# ST_LINK_V2.net
KiCad netlist of a schematic drawn in Altium Designer
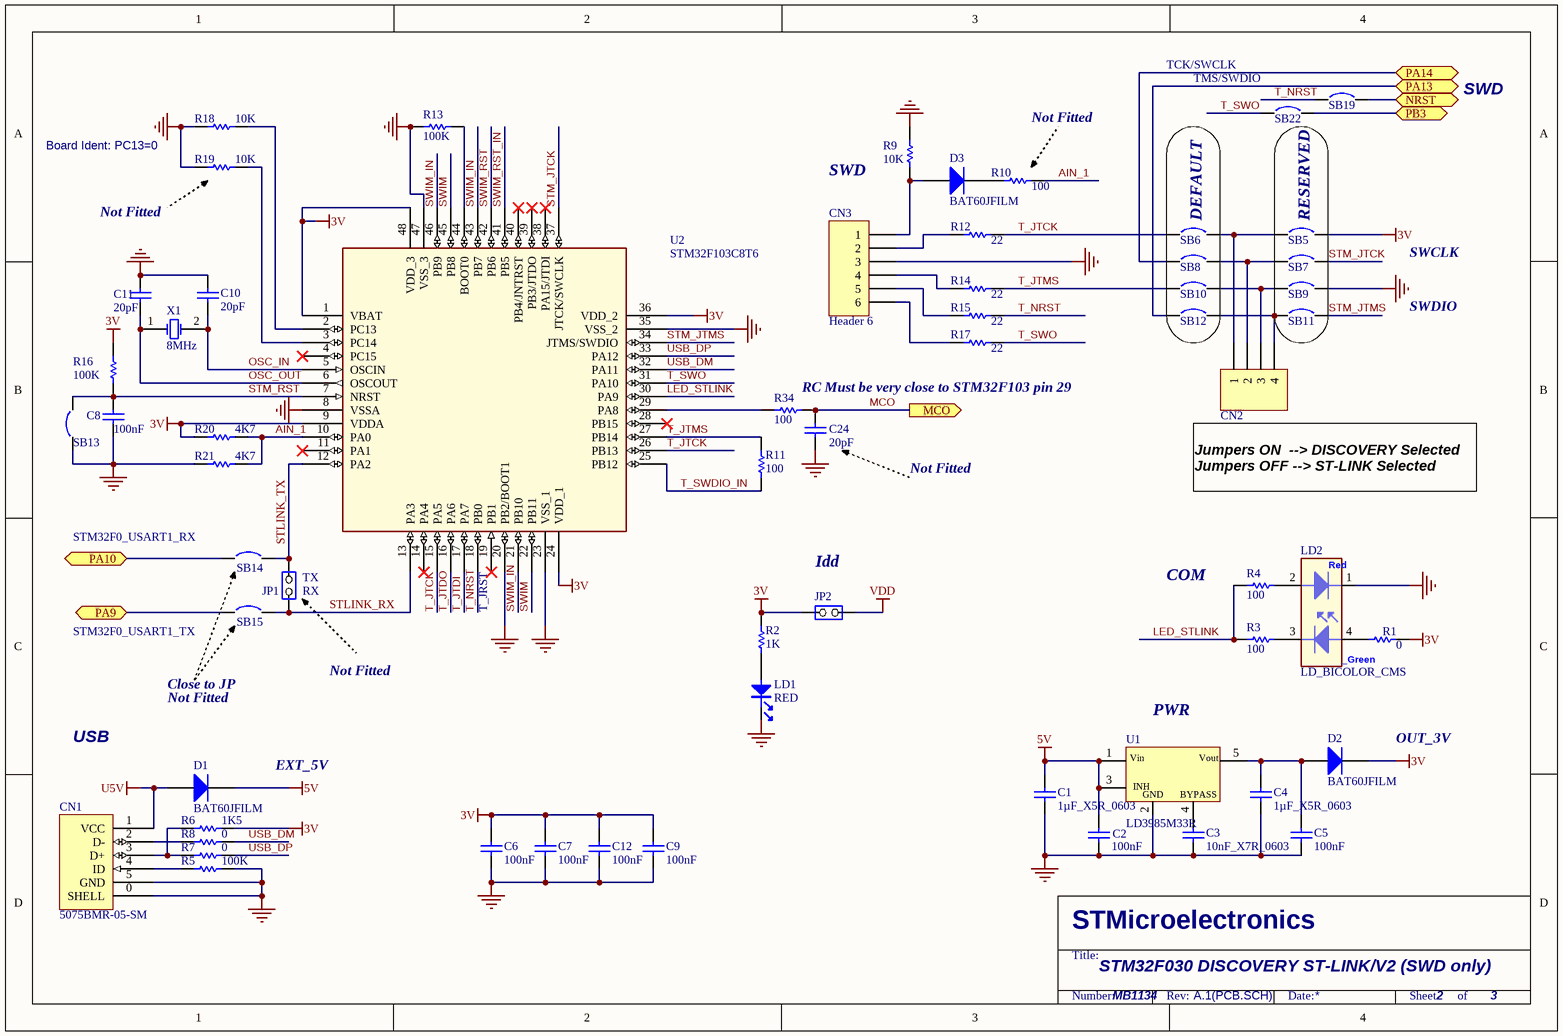
[diagram p0: ST_LINK_V2.SCHDOC]

(export (version "E")
  (design (tool "Eeschema 10.0.6"))
  (components
    (comp (ref "C1")
      (value "1µF_X5R_0603")
      (footprint "0603C")
      (description "0603  X5R 1µF")
      (fields (field (name "TOLERANCE") "10%"))
      (libsource (lib "MCD_TOOLS") (part "CAP SMD 0603  X5R 1µF 25V 10%"))
    )
    (comp (ref "C2")
      (value "100nF")
      (footprint "0603C")
      (description "Capacitor")
      (fields (field (name "PUBLISHER") "Altium Limited"))
      (libsource (lib "MCD_TOOLS") (part "Cap"))
    )
    (comp (ref "C3")
      (value "10nF_X7R_0603")
      (footprint "0603C")
      (description "0603  X7R 10NF")
      (fields (field (name "TOLERANCE") "10%"))
      (libsource (lib "MCD_TOOLS") (part "CAP SMD 0603  X7R 10000PF 50V 10%"))
    )
    (comp (ref "C4")
      (value "1µF_X5R_0603")
      (footprint "0603C")
      (description "0603  X5R 1µF")
      (fields (field (name "TOLERANCE") "10%"))
      (libsource (lib "MCD_TOOLS") (part "CAP SMD 0603  X5R 1µF 25V 10%"))
    )
    (comp (ref "C5")
      (value "100nF")
      (footprint "0603C")
      (description "Capacitor")
      (fields (field (name "PUBLISHER") "Altium Limited"))
      (libsource (lib "MCD_TOOLS") (part "Cap"))
    )
    (comp (ref "C6")
      (value "100nF")
      (footprint "0402C")
      (description "Capacitor")
      (fields (field (name "PUBLISHER") "Altium Limited"))
      (libsource (lib "MCD_TOOLS") (part "Cap"))
    )
    (comp (ref "C7")
      (value "100nF")
      (footprint "0402C")
      (description "Capacitor")
      (fields (field (name "PUBLISHER") "Altium Limited"))
      (libsource (lib "MCD_TOOLS") (part "Cap"))
    )
    (comp (ref "C8")
      (value "100nF")
      (footprint "0402C")
      (description "Capacitor")
      (fields (field (name "PUBLISHER") "Altium Limited"))
      (libsource (lib "MCD_TOOLS") (part "Cap"))
    )
    (comp (ref "C9")
      (value "100nF")
      (footprint "0402C")
      (description "Capacitor")
      (fields (field (name "PUBLISHER") "Altium Limited"))
      (libsource (lib "MCD_TOOLS") (part "Cap"))
    )
    (comp (ref "C10")
      (value "20pF")
      (footprint "0402C")
      (description "Capacitor")
      (fields (field (name "PUBLISHER") "Altium Limited"))
      (libsource (lib "MCD_TOOLS") (part "Cap"))
    )
    (comp (ref "C11")
      (value "20pF")
      (footprint "0402C")
      (description "Capacitor")
      (fields (field (name "PUBLISHER") "Altium Limited"))
      (libsource (lib "MCD_TOOLS") (part "Cap"))
    )
    (comp (ref "C12")
      (value "100nF")
      (footprint "0402C")
      (description "Capacitor")
      (fields (field (name "PUBLISHER") "Altium Limited"))
      (libsource (lib "MCD_TOOLS") (part "Cap"))
    )
    (comp (ref "C24")
      (value "20pF")
      (footprint "0402C")
      (description "Capacitor")
      (fields (field (name "PUBLISHER") "Altium Limited"))
      (libsource (lib "MCD_TOOLS") (part "Cap"))
    )
    (comp (ref "CN1")
      (value "5075BMR-05-SM")
      (footprint "USB-MINI-B-SMD")
      (libsource (lib "MCD_TOOLS") (part "USB-MINI-typeB connector"))
    )
    (comp (ref "CN2")
      (value "Header 4")
      (footprint "Header 4")
      (description "Header 4x1 with 2 Jumpers")
      (fields (field (name "PUBLISHER") "Altium Limited"))
      (libsource (lib "MCD_TOOLS") (part "Header 4"))
    )
    (comp (ref "CN3")
      (value "Header 6")
      (footprint "HDR1X6")
      (description "Header, 6-Pin")
      (fields (field (name "PUBLISHER") "Altium Limited"))
      (libsource (lib "Miscellaneous Connectors") (part "Header 6"))
    )
    (comp (ref "D1")
      (value "BAT60JFILM")
      (footprint "SOD323/A")
      (fields (field (name "PUBLISHER") "Altium Limited"))
      (libsource (lib "MCD_TOOLS") (part "BAT60JFILM"))
    )
    (comp (ref "D2")
      (value "BAT60JFILM")
      (footprint "SOD323/A")
      (fields (field (name "PUBLISHER") "Altium Limited"))
      (libsource (lib "MCD_TOOLS") (part "BAT60JFILM"))
    )
    (comp (ref "D3")
      (value "BAT60JFILM")
      (footprint "SOD323/A")
      (fields (field (name "PUBLISHER") "Altium Limited"))
      (libsource (lib "MCD_TOOLS") (part "BAT60JFILM"))
    )
    (comp (ref "JP1") (value "~") (footprint "SIP2/2.54") (libsource (lib "MCD_TOOLS") (part "JP2")))
    (comp (ref "JP2")
      (value "~")
      (footprint "SIP2/2.54")
      (description "Header 2x1 with Jumper")
      (libsource (lib "MCD_TOOLS") (part "JP2"))
    )
    (comp (ref "LD1") (value "RED") (footprint "0603D") (libsource (lib "MCD_TOOLS") (part "PHOTO")))
    (comp (ref "LD2")
      (value "LD_BICOLOR_CMS")
      (footprint "HSMF-A201")
      (description "Bicolor Led")
      (libsource (lib "MCD_TOOLS") (part "LD_BICOLOR_CMS"))
    )
    (comp (ref "R1")
      (value "0")
      (footprint "0402R")
      (description "Resistor")
      (fields (field (name "PUBLISHER") "Altium Limited"))
      (libsource (lib "MCD_TOOLS") (part "res1"))
    )
    (comp (ref "R2")
      (value "1K")
      (footprint "0402R")
      (description "Resistor")
      (fields (field (name "PUBLISHER") "Altium Limited"))
      (libsource (lib "MCD_TOOLS") (part "res1"))
    )
    (comp (ref "R3")
      (value "100")
      (footprint "0402R")
      (description "Resistor")
      (fields (field (name "PUBLISHER") "Altium Limited"))
      (libsource (lib "MCD_TOOLS") (part "res1"))
    )
    (comp (ref "R4")
      (value "100")
      (footprint "0402R")
      (description "Resistor")
      (fields (field (name "PUBLISHER") "Altium Limited"))
      (libsource (lib "MCD_TOOLS") (part "res1"))
    )
    (comp (ref "R5")
      (value "100K")
      (footprint "0402R")
      (description "Resistor")
      (fields (field (name "PUBLISHER") "Altium Limited"))
      (libsource (lib "MB915_1") (part "res1"))
    )
    (comp (ref "R6")
      (value "1K5")
      (footprint "0402R")
      (description "Resistor")
      (fields (field (name "PUBLISHER") "Altium Limited"))
      (libsource (lib "MB915_1") (part "res1"))
    )
    (comp (ref "R7")
      (value "0")
      (footprint "0603R-GS")
      (description "Resistor")
      (fields (field (name "PUBLISHER") "Altium Limited"))
      (libsource (lib "MB915_1") (part "res1"))
    )
    (comp (ref "R8")
      (value "0")
      (footprint "0603R-GS")
      (description "Resistor")
      (fields (field (name "PUBLISHER") "Altium Limited"))
      (libsource (lib "MB915_1") (part "res1"))
    )
    (comp (ref "R9")
      (value "10K")
      (footprint "0402R")
      (description "Resistor")
      (fields (field (name "PUBLISHER") "Altium Limited"))
      (libsource (lib "MB915_1") (part "res1"))
    )
    (comp (ref "R10")
      (value "100")
      (footprint "0402R")
      (description "Resistor")
      (fields (field (name "PUBLISHER") "Altium Limited"))
      (libsource (lib "MCD_TOOLS") (part "res1"))
    )
    (comp (ref "R11")
      (value "100")
      (footprint "0402R")
      (description "Resistor")
      (fields (field (name "PUBLISHER") "Altium Limited"))
      (libsource (lib "MCD_TOOLS") (part "res1"))
    )
    (comp (ref "R12")
      (value "22")
      (footprint "0402R")
      (description "Resistor")
      (fields (field (name "PUBLISHER") "Altium Limited"))
      (libsource (lib "MCD_TOOLS") (part "res1"))
    )
    (comp (ref "R13")
      (value "100K")
      (footprint "0402R")
      (description "Resistor")
      (fields (field (name "PUBLISHER") "Altium Limited"))
      (libsource (lib "MCD_TOOLS") (part "res1"))
    )
    (comp (ref "R14")
      (value "22")
      (footprint "0402R")
      (description "Resistor")
      (fields (field (name "PUBLISHER") "Altium Limited"))
      (libsource (lib "MCD_TOOLS") (part "res1"))
    )
    (comp (ref "R15")
      (value "22")
      (footprint "0402R")
      (description "Resistor")
      (fields (field (name "PUBLISHER") "Altium Limited"))
      (libsource (lib "MCD_TOOLS") (part "res1"))
    )
    (comp (ref "R16")
      (value "100K")
      (footprint "0402R")
      (description "Resistor")
      (fields (field (name "PUBLISHER") "Altium Limited"))
      (libsource (lib "MCD_TOOLS") (part "res1"))
    )
    (comp (ref "R17")
      (value "22")
      (footprint "0402R")
      (description "Resistor")
      (fields (field (name "PUBLISHER") "Altium Limited"))
      (libsource (lib "MCD_TOOLS") (part "res1"))
    )
    (comp (ref "R18")
      (value "10K")
      (footprint "0402R")
      (description "Resistor")
      (fields (field (name "PUBLISHER") "Altium Limited"))
      (libsource (lib "MCD_TOOLS") (part "res1"))
    )
    (comp (ref "R19")
      (value "10K")
      (footprint "0402R")
      (description "Resistor")
      (fields (field (name "PUBLISHER") "Altium Limited"))
      (libsource (lib "MCD_TOOLS") (part "res1"))
    )
    (comp (ref "R20")
      (value "4K7")
      (footprint "0402R")
      (description "Resistor")
      (fields (field (name "PUBLISHER") "Altium Limited"))
      (libsource (lib "MCD_TOOLS") (part "res1"))
    )
    (comp (ref "R21")
      (value "4K7")
      (footprint "0402R")
      (description "Resistor")
      (fields (field (name "PUBLISHER") "Altium Limited"))
      (libsource (lib "MCD_TOOLS") (part "res1"))
    )
    (comp (ref "R34")
      (value "100")
      (footprint "0402R")
      (description "Resistor")
      (fields (field (name "PUBLISHER") "Altium Limited"))
      (libsource (lib "MCD_TOOLS") (part "res1"))
    )
    (comp (ref "SB5")
      (value "Circuit Breaker")
      (footprint "JP2_SMD")
      (fields (field (name "PUBLISHER") "Altium Limited"))
      (libsource (lib "MB915") (part "Circuit Breaker"))
    )
    (comp (ref "SB6")
      (value "Circuit Breaker")
      (footprint "JP2_SMD")
      (fields (field (name "PUBLISHER") "Altium Limited"))
      (libsource (lib "MB915") (part "Circuit Breaker"))
    )
    (comp (ref "SB7")
      (value "Circuit Breaker")
      (footprint "JP2_SMD")
      (fields (field (name "PUBLISHER") "Altium Limited"))
      (libsource (lib "MB915") (part "Circuit Breaker"))
    )
    (comp (ref "SB8")
      (value "Circuit Breaker")
      (footprint "JP2_SMD")
      (fields (field (name "PUBLISHER") "Altium Limited"))
      (libsource (lib "MB915") (part "Circuit Breaker"))
    )
    (comp (ref "SB9")
      (value "Circuit Breaker")
      (footprint "JP2_SMD")
      (fields (field (name "PUBLISHER") "Altium Limited"))
      (libsource (lib "MB915") (part "Circuit Breaker"))
    )
    (comp (ref "SB10")
      (value "Circuit Breaker")
      (footprint "JP2_SMD")
      (fields (field (name "PUBLISHER") "Altium Limited"))
      (libsource (lib "MB915") (part "Circuit Breaker"))
    )
    (comp (ref "SB11")
      (value "Circuit Breaker")
      (footprint "JP2_SMD")
      (fields (field (name "PUBLISHER") "Altium Limited"))
      (libsource (lib "MB915") (part "Circuit Breaker"))
    )
    (comp (ref "SB12")
      (value "Circuit Breaker")
      (footprint "JP2_SMD")
      (fields (field (name "PUBLISHER") "Altium Limited"))
      (libsource (lib "MB915") (part "Circuit Breaker"))
    )
    (comp (ref "SB13")
      (value "Circuit Breaker")
      (footprint "JP2_SMD")
      (fields (field (name "PUBLISHER") "Altium Limited"))
      (libsource (lib "MCD_TOOLS") (part "Circuit Breaker"))
    )
    (comp (ref "SB14")
      (value "Circuit Breaker")
      (footprint "JP2_SMD")
      (fields (field (name "PUBLISHER") "Altium Limited"))
      (libsource (lib "MCD_TOOLS") (part "Circuit Breaker"))
    )
    (comp (ref "SB15")
      (value "Circuit Breaker")
      (footprint "JP2_SMD")
      (fields (field (name "PUBLISHER") "Altium Limited"))
      (libsource (lib "MCD_TOOLS") (part "Circuit Breaker"))
    )
    (comp (ref "SB19")
      (value "Circuit Breaker")
      (footprint "JP2_SMD")
      (fields (field (name "PUBLISHER") "Altium Limited"))
      (libsource (lib "MCD_TOOLS") (part "Circuit Breaker"))
    )
    (comp (ref "SB22")
      (value "Circuit Breaker")
      (footprint "JP2_SMD")
      (fields (field (name "PUBLISHER") "Altium Limited"))
      (libsource (lib "MCD_TOOLS") (part "Circuit Breaker"))
    )
    (comp (ref "U1")
      (value "LD3985M33R")
      (footprint "SOT-23-5L")
      (description "Ultra low drop-low noise BiCMOS voltage, regulators low ESR capacitors compatible")
      (libsource (lib "MCD_TOOLS") (part "LD3985M33R"))
    )
    (comp (ref "U2")
      (value "STM32F103C8T6")
      (footprint "QFP48 7X7")
      (description "Medium-density performance line ARM-based 32-bit MCU with 64KB Flash, USB, CAN, 7 timers, 2 ADCs")
      (libsource (lib "MCD_TOOLS") (part "STM32F103C8T6"))
    )
    (comp (ref "X1")
      (value "8MHz")
      (footprint "XTAL1")
      (description "Crystal Oscillator")
      (fields (field (name "PUBLISHER") "Altium Limited"))
      (libsource (lib "MCD_TOOLS") (part "XTAL"))
    )
  )
  (nets
    (net (code "1") (name "/AIN_1") (class "Default")
      (node (ref "R10") (pin "2") (pinfunction "2_2") (pintype "passive"))
      (node (ref "R20") (pin "2") (pinfunction "2_2") (pintype "passive"))
      (node (ref "R21") (pin "2") (pinfunction "2_2") (pintype "passive"))
      (node (ref "U2") (pin "10") (pinfunction "PA0_10") (pintype "bidirectional"))
    )
    (net (code "2") (name "/LED_STLINK") (class "Default")
      (node (ref "R3") (pin "1") (pinfunction "1_1") (pintype "passive"))
      (node (ref "R4") (pin "1") (pinfunction "1_1") (pintype "passive"))
      (node (ref "U2") (pin "30") (pinfunction "PA9_30") (pintype "bidirectional"))
    )
    (net (code "3") (name "/MCO") (class "Default")
      (node (ref "C24") (pin "1") (pinfunction "1_1") (pintype "passive"))
      (node (ref "R34") (pin "2") (pinfunction "2_2") (pintype "passive"))
    )
    (net (code "4") (name "/NRST") (class "Default")
      (node (ref "SB19") (pin "2") (pinfunction "2_2") (pintype "passive"))
    )
    (net (code "5") (name "/OSC_IN") (class "Default")
      (node (ref "C10") (pin "2") (pinfunction "2_2") (pintype "passive"))
      (node (ref "U2") (pin "5") (pinfunction "OSCIN_5") (pintype "input"))
      (node (ref "X1") (pin "2") (pinfunction "OSC2_2") (pintype "passive"))
    )
    (net (code "6") (name "/OSC_OUT") (class "Default")
      (node (ref "C11") (pin "2") (pinfunction "2_2") (pintype "passive"))
      (node (ref "U2") (pin "6") (pinfunction "OSCOUT_6") (pintype "output"))
      (node (ref "X1") (pin "1") (pinfunction "OSC1_1") (pintype "passive"))
    )
    (net (code "7") (name "/PA9") (class "Default")
      (node (ref "SB15") (pin "1") (pinfunction "1_1") (pintype "passive"))
    )
    (net (code "8") (name "/PA10") (class "Default")
      (node (ref "SB14") (pin "1") (pinfunction "1_1") (pintype "passive"))
    )
    (net (code "9") (name "/PA13") (class "Default")
      (node (ref "SB12") (pin "1") (pinfunction "1_1") (pintype "passive"))
    )
    (net (code "10") (name "/PA14") (class "Default")
      (node (ref "SB8") (pin "1") (pinfunction "1_1") (pintype "passive"))
    )
    (net (code "11") (name "/PB3") (class "Default")
      (node (ref "SB22") (pin "2") (pinfunction "2_2") (pintype "passive"))
    )
    (net (code "12") (name "/STLINK_RX") (class "Default")
      (node (ref "JP1") (pin "1") (pinfunction "COMMON_1") (pintype "passive"))
      (node (ref "SB15") (pin "2") (pinfunction "2_2") (pintype "passive"))
      (node (ref "U2") (pin "13") (pinfunction "PA3_13") (pintype "bidirectional"))
    )
    (net (code "13") (name "/STLINK_TX") (class "Default")
      (node (ref "JP1") (pin "2") (pinfunction "NO_2") (pintype "passive"))
      (node (ref "SB14") (pin "2") (pinfunction "2_2") (pintype "passive"))
      (node (ref "U2") (pin "12") (pinfunction "PA2_12") (pintype "bidirectional"))
    )
    (net (code "14") (name "/STM_JTCK") (class "Default")
      (node (ref "SB7") (pin "2") (pinfunction "2_2") (pintype "passive"))
      (node (ref "U2") (pin "37") (pinfunction "JTCK/SWCLK_37") (pintype "bidirectional"))
    )
    (net (code "15") (name "/STM_JTMS") (class "Default")
      (node (ref "SB11") (pin "2") (pinfunction "2_2") (pintype "passive"))
      (node (ref "U2") (pin "34") (pinfunction "JTMS/SWDIO_34") (pintype "bidirectional"))
    )
    (net (code "16") (name "/STM_RST") (class "Default")
      (node (ref "C8") (pin "2") (pinfunction "2_2") (pintype "passive"))
      (node (ref "R16") (pin "1") (pinfunction "1_1") (pintype "passive"))
      (node (ref "SB13") (pin "2") (pinfunction "2_2") (pintype "passive"))
      (node (ref "U2") (pin "7") (pinfunction "NRST_7") (pintype "input"))
    )
    (net (code "17") (name "/SWIM") (class "Default")
      (node (ref "U2") (pin "22") (pinfunction "PB11_22") (pintype "bidirectional"))
      (node (ref "U2") (pin "45") (pinfunction "PB8_45") (pintype "bidirectional"))
    )
    (net (code "18") (name "/SWIM_IN") (class "Default")
      (node (ref "U2") (pin "21") (pinfunction "PB10_21") (pintype "bidirectional"))
      (node (ref "U2") (pin "43") (pinfunction "PB7_43") (pintype "bidirectional"))
      (node (ref "U2") (pin "46") (pinfunction "PB9_46") (pintype "bidirectional"))
    )
    (net (code "19") (name "/SWIM_RST") (class "Default")
      (node (ref "U2") (pin "42") (pinfunction "PB6_42") (pintype "bidirectional"))
    )
    (net (code "20") (name "/SWIM_RST_IN") (class "Default")
      (node (ref "U2") (pin "41") (pinfunction "PB5_41") (pintype "bidirectional"))
    )
    (net (code "21") (name "/T_JTCK") (class "Default")
      (node (ref "R12") (pin "2") (pinfunction "2_2") (pintype "passive"))
      (node (ref "SB6") (pin "1") (pinfunction "1_1") (pintype "passive"))
      (node (ref "U2") (pin "15") (pinfunction "PA5_15") (pintype "bidirectional"))
      (node (ref "U2") (pin "26") (pinfunction "PB13_26") (pintype "bidirectional"))
    )
    (net (code "22") (name "/T_JTDI") (class "Default")
      (node (ref "U2") (pin "17") (pinfunction "PA7_17") (pintype "bidirectional"))
    )
    (net (code "23") (name "/T_JTDO") (class "Default")
      (node (ref "U2") (pin "16") (pinfunction "PA6_16") (pintype "bidirectional"))
    )
    (net (code "24") (name "/T_JTMS") (class "Default")
      (node (ref "R11") (pin "2") (pinfunction "2_2") (pintype "passive"))
      (node (ref "R14") (pin "2") (pinfunction "2_2") (pintype "passive"))
      (node (ref "SB10") (pin "1") (pinfunction "1_1") (pintype "passive"))
      (node (ref "U2") (pin "27") (pinfunction "PB14_27") (pintype "bidirectional"))
    )
    (net (code "25") (name "/T_NRST") (class "Default")
      (node (ref "R15") (pin "2") (pinfunction "2_2") (pintype "passive"))
      (node (ref "SB19") (pin "1") (pinfunction "1_1") (pintype "passive"))
      (node (ref "U2") (pin "18") (pinfunction "PB0_18") (pintype "bidirectional"))
    )
    (net (code "26") (name "/T_SWDIO_IN") (class "Default")
      (node (ref "R11") (pin "1") (pinfunction "1_1") (pintype "passive"))
      (node (ref "U2") (pin "25") (pinfunction "PB12_25") (pintype "bidirectional"))
    )
    (net (code "27") (name "/T_SWO") (class "Default")
      (node (ref "R17") (pin "2") (pinfunction "2_2") (pintype "passive"))
      (node (ref "SB22") (pin "1") (pinfunction "1_1") (pintype "passive"))
      (node (ref "U2") (pin "31") (pinfunction "PA10_31") (pintype "bidirectional"))
    )
    (net (code "28") (name "/USB_DM") (class "Default")
      (node (ref "R8") (pin "2") (pinfunction "2_2") (pintype "passive"))
      (node (ref "U2") (pin "32") (pinfunction "PA11_32") (pintype "bidirectional"))
    )
    (net (code "29") (name "/USB_DP") (class "Default")
      (node (ref "R7") (pin "2") (pinfunction "2_2") (pintype "passive"))
      (node (ref "U2") (pin "33") (pinfunction "PA12_33") (pintype "bidirectional"))
    )
    (net (code "30") (name "3V") (class "Default")
      (node (ref "C12") (pin "1") (pinfunction "1_1") (pintype "passive"))
      (node (ref "C6") (pin "2") (pinfunction "2_2") (pintype "passive"))
      (node (ref "C7") (pin "2") (pinfunction "2_2") (pintype "passive"))
      (node (ref "C9") (pin "2") (pinfunction "2_2") (pintype "passive"))
      (node (ref "D2") (pin "2") (pinfunction "K_2") (pintype "passive"))
      (node (ref "JP2") (pin "1") (pinfunction "COMMON_1") (pintype "passive"))
      (node (ref "R1") (pin "2") (pinfunction "2_2") (pintype "passive"))
      (node (ref "R16") (pin "2") (pinfunction "2_2") (pintype "passive"))
      (node (ref "R2") (pin "2") (pinfunction "2_2") (pintype "passive"))
      (node (ref "R20") (pin "1") (pinfunction "1_1") (pintype "passive"))
      (node (ref "R6") (pin "2") (pinfunction "2_2") (pintype "passive"))
      (node (ref "SB5") (pin "2") (pinfunction "2_2") (pintype "passive"))
      (node (ref "U2") (pin "1") (pinfunction "VBAT_1") (pintype "power_in"))
      (node (ref "U2") (pin "24") (pinfunction "VDD_1_24") (pintype "power_in"))
      (node (ref "U2") (pin "36") (pinfunction "VDD_2_36") (pintype "power_in"))
      (node (ref "U2") (pin "48") (pinfunction "VDD_3_48") (pintype "power_in"))
      (node (ref "U2") (pin "9") (pinfunction "VDDA_9") (pintype "power_in"))
    )
    (net (code "31") (name "5V") (class "Default")
      (node (ref "C1") (pin "2") (pinfunction "2_2") (pintype "passive"))
      (node (ref "C2") (pin "2") (pinfunction "2_2") (pintype "passive"))
      (node (ref "D1") (pin "2") (pinfunction "K_2") (pintype "passive"))
      (node (ref "U1") (pin "1") (pinfunction "Vin_1") (pintype "passive"))
      (node (ref "U1") (pin "3") (pinfunction "CE_3") (pintype "passive"))
    )
    (net (code "32") (name "GND") (class "Default")
      (node (ref "C1") (pin "1") (pinfunction "1_1") (pintype "passive"))
      (node (ref "C10") (pin "1") (pinfunction "1_1") (pintype "passive"))
      (node (ref "C11") (pin "1") (pinfunction "1_1") (pintype "passive"))
      (node (ref "C12") (pin "2") (pinfunction "2_2") (pintype "passive"))
      (node (ref "C2") (pin "1") (pinfunction "1_1") (pintype "passive"))
      (node (ref "C24") (pin "2") (pinfunction "2_2") (pintype "passive"))
      (node (ref "C3") (pin "1") (pinfunction "1_1") (pintype "passive"))
      (node (ref "C4") (pin "2") (pinfunction "2_2") (pintype "passive"))
      (node (ref "C5") (pin "1") (pinfunction "1_1") (pintype "passive"))
      (node (ref "C6") (pin "1") (pinfunction "1_1") (pintype "passive"))
      (node (ref "C7") (pin "1") (pinfunction "1_1") (pintype "passive"))
      (node (ref "C8") (pin "1") (pinfunction "1_1") (pintype "passive"))
      (node (ref "C9") (pin "1") (pinfunction "1_1") (pintype "passive"))
      (node (ref "CN1") (pin "0") (pinfunction "SHELL_0") (pintype "power_in"))
      (node (ref "CN1") (pin "5") (pinfunction "GND_5") (pintype "power_in"))
      (node (ref "CN3") (pin "3") (pinfunction "3_3") (pintype "passive"))
      (node (ref "LD1") (pin "2") (pintype "passive"))
      (node (ref "LD2") (pin "1") (pinfunction "1_1") (pintype "passive"))
      (node (ref "R13") (pin "1") (pinfunction "1_1") (pintype "passive"))
      (node (ref "R18") (pin "1") (pinfunction "1_1") (pintype "passive"))
      (node (ref "R19") (pin "1") (pinfunction "1_1") (pintype "passive"))
      (node (ref "R21") (pin "1") (pinfunction "1_1") (pintype "passive"))
      (node (ref "R5") (pin "2") (pinfunction "2_2") (pintype "passive"))
      (node (ref "R9") (pin "2") (pinfunction "2_2") (pintype "passive"))
      (node (ref "SB13") (pin "1") (pinfunction "1_1") (pintype "passive"))
      (node (ref "SB9") (pin "2") (pinfunction "2_2") (pintype "passive"))
      (node (ref "U1") (pin "2") (pinfunction "GND_2") (pintype "passive"))
      (node (ref "U2") (pin "20") (pinfunction "PB2/BOOT1_20") (pintype "bidirectional"))
      (node (ref "U2") (pin "23") (pinfunction "VSS_1_23") (pintype "power_in"))
      (node (ref "U2") (pin "35") (pinfunction "VSS_2_35") (pintype "power_in"))
      (node (ref "U2") (pin "47") (pinfunction "VSS_3_47") (pintype "power_in"))
      (node (ref "U2") (pin "8") (pinfunction "VSSA_8") (pintype "power_in"))
    )
    (net (code "33") (name "Net-(CN1-D+)") (class "Default")
      (node (ref "CN1") (pin "3") (pinfunction "D+_3") (pintype "bidirectional"))
      (node (ref "R6") (pin "1") (pinfunction "1_1") (pintype "passive"))
      (node (ref "R7") (pin "1") (pinfunction "1_1") (pintype "passive"))
    )
    (net (code "34") (name "Net-(CN1-D-)") (class "Default")
      (node (ref "CN1") (pin "2") (pinfunction "D-_2") (pintype "bidirectional"))
      (node (ref "R8") (pin "1") (pinfunction "1_1") (pintype "passive"))
    )
    (net (code "35") (name "Net-(CN1-ID)") (class "Default")
      (node (ref "CN1") (pin "4") (pinfunction "ID_4") (pintype "input"))
      (node (ref "R5") (pin "1") (pinfunction "1_1") (pintype "passive"))
    )
    (net (code "36") (name "Net-(CN2-Pad1)") (class "Default")
      (node (ref "CN2") (pin "1") (pinfunction "1_1") (pintype "passive"))
      (node (ref "SB5") (pin "1") (pinfunction "1_1") (pintype "passive"))
      (node (ref "SB6") (pin "2") (pinfunction "2_2") (pintype "passive"))
    )
    (net (code "37") (name "Net-(CN2-Pad2)") (class "Default")
      (node (ref "CN2") (pin "2") (pinfunction "2_2") (pintype "passive"))
      (node (ref "SB7") (pin "1") (pinfunction "1_1") (pintype "passive"))
      (node (ref "SB8") (pin "2") (pinfunction "2_2") (pintype "passive"))
    )
    (net (code "38") (name "Net-(CN2-Pad3)") (class "Default")
      (node (ref "CN2") (pin "3") (pinfunction "3_3") (pintype "passive"))
      (node (ref "SB10") (pin "2") (pinfunction "2_2") (pintype "passive"))
      (node (ref "SB9") (pin "1") (pinfunction "1_1") (pintype "passive"))
    )
    (net (code "39") (name "Net-(CN2-Pad4)") (class "Default")
      (node (ref "CN2") (pin "4") (pinfunction "4_4") (pintype "passive"))
      (node (ref "SB11") (pin "1") (pinfunction "1_1") (pintype "passive"))
      (node (ref "SB12") (pin "2") (pinfunction "2_2") (pintype "passive"))
    )
    (net (code "40") (name "Net-(CN3-Pad2)") (class "Default")
      (node (ref "CN3") (pin "2") (pinfunction "2_2") (pintype "passive"))
      (node (ref "R12") (pin "1") (pinfunction "1_1") (pintype "passive"))
    )
    (net (code "41") (name "Net-(CN3-Pad4)") (class "Default")
      (node (ref "CN3") (pin "4") (pinfunction "4_4") (pintype "passive"))
      (node (ref "R14") (pin "1") (pinfunction "1_1") (pintype "passive"))
    )
    (net (code "42") (name "Net-(CN3-Pad5)") (class "Default")
      (node (ref "CN3") (pin "5") (pinfunction "5_5") (pintype "passive"))
      (node (ref "R15") (pin "1") (pinfunction "1_1") (pintype "passive"))
    )
    (net (code "43") (name "Net-(CN3-Pad6)") (class "Default")
      (node (ref "CN3") (pin "6") (pinfunction "6_6") (pintype "passive"))
      (node (ref "R17") (pin "1") (pinfunction "1_1") (pintype "passive"))
    )
    (net (code "44") (name "Net-(D2-A)") (class "Default")
      (node (ref "C4") (pin "1") (pinfunction "1_1") (pintype "passive"))
      (node (ref "C5") (pin "2") (pinfunction "2_2") (pintype "passive"))
      (node (ref "D2") (pin "1") (pinfunction "A_1") (pintype "passive"))
      (node (ref "U1") (pin "5") (pinfunction "Vout_5") (pintype "passive"))
    )
    (net (code "45") (name "Net-(D3-A)") (class "Default")
      (node (ref "CN3") (pin "1") (pinfunction "1_1") (pintype "passive"))
      (node (ref "D3") (pin "1") (pinfunction "A_1") (pintype "passive"))
      (node (ref "R9") (pin "1") (pinfunction "1_1") (pintype "passive"))
    )
    (net (code "46") (name "Net-(D3-K)") (class "Default")
      (node (ref "D3") (pin "2") (pinfunction "K_2") (pintype "passive"))
      (node (ref "R10") (pin "1") (pinfunction "1_1") (pintype "passive"))
    )
    (net (code "47") (name "Net-(LD1-Pad1)") (class "Default")
      (node (ref "LD1") (pin "1") (pintype "passive"))
      (node (ref "R2") (pin "1") (pinfunction "1_1") (pintype "passive"))
    )
    (net (code "48") (name "Net-(LD2-Pad2)") (class "Default")
      (node (ref "LD2") (pin "2") (pinfunction "2_2") (pintype "passive"))
      (node (ref "R4") (pin "2") (pinfunction "2_2") (pintype "passive"))
    )
    (net (code "49") (name "Net-(LD2-Pad3)") (class "Default")
      (node (ref "LD2") (pin "3") (pinfunction "3_3") (pintype "passive"))
      (node (ref "R3") (pin "2") (pinfunction "2_2") (pintype "passive"))
    )
    (net (code "50") (name "Net-(LD2-Pad4)") (class "Default")
      (node (ref "LD2") (pin "4") (pinfunction "4_4") (pintype "passive"))
      (node (ref "R1") (pin "1") (pinfunction "1_1") (pintype "passive"))
    )
    (net (code "51") (name "Net-(U1-BYPASS)") (class "Default")
      (node (ref "C3") (pin "2") (pinfunction "2_2") (pintype "passive"))
      (node (ref "U1") (pin "4") (pinfunction "BYPASS_4") (pintype "passive"))
    )
    (net (code "52") (name "Net-(U2-BOOT0)") (class "Default")
      (node (ref "R13") (pin "2") (pinfunction "2_2") (pintype "passive"))
      (node (ref "U2") (pin "44") (pinfunction "BOOT0_44") (pintype "bidirectional"))
    )
    (net (code "53") (name "Net-(U2-PA8)") (class "Default")
      (node (ref "R34") (pin "1") (pinfunction "1_1") (pintype "passive"))
      (node (ref "U2") (pin "29") (pinfunction "PA8_29") (pintype "bidirectional"))
    )
    (net (code "54") (name "Net-(U2-PC13)") (class "Default")
      (node (ref "R18") (pin "2") (pinfunction "2_2") (pintype "passive"))
      (node (ref "U2") (pin "2") (pinfunction "PC13_2") (pintype "bidirectional"))
    )
    (net (code "55") (name "Net-(U2-PC14)") (class "Default")
      (node (ref "R19") (pin "2") (pinfunction "2_2") (pintype "passive"))
      (node (ref "U2") (pin "3") (pinfunction "PC14_3") (pintype "bidirectional"))
    )
    (net (code "56") (name "U5V") (class "Default")
      (node (ref "CN1") (pin "1") (pinfunction "VCC_1") (pintype "power_in"))
      (node (ref "D1") (pin "1") (pinfunction "A_1") (pintype "passive"))
    )
    (net (code "57") (name "VDD") (class "Default")
      (node (ref "JP2") (pin "2") (pinfunction "NO_2") (pintype "passive"))
    )
    (net (code "58") (name "unconnected-(U2-PA1-Pad11)") (class "Default")
      (node (ref "U2") (pin "11") (pinfunction "PA1_11") (pintype "bidirectional+no_connect"))
    )
    (net (code "59") (name "unconnected-(U2-PA4-Pad14)") (class "Default")
      (node (ref "U2") (pin "14") (pinfunction "PA4_14") (pintype "bidirectional+no_connect"))
    )
    (net (code "60") (name "unconnected-(U2-PA15{slash}JTDI-Pad38)") (class "Default")
      (node (ref "U2") (pin "38") (pinfunction "PA15/JTDI_38") (pintype "bidirectional+no_connect"))
    )
    (net (code "61") (name "unconnected-(U2-PB1-Pad19)") (class "Default")
      (node (ref "U2") (pin "19") (pinfunction "PB1_19") (pintype "input+no_connect"))
    )
    (net (code "62") (name "unconnected-(U2-PB3{slash}JTDO-Pad39)") (class "Default")
      (node (ref "U2") (pin "39") (pinfunction "PB3/JTDO_39") (pintype "bidirectional+no_connect"))
    )
    (net (code "63") (name "unconnected-(U2-PB4{slash}JNTRST-Pad40)") (class "Default")
      (node (ref "U2") (pin "40") (pinfunction "PB4/JNTRST_40") (pintype "bidirectional+no_connect"))
    )
    (net (code "64") (name "unconnected-(U2-PB15-Pad28)") (class "Default")
      (node (ref "U2") (pin "28") (pinfunction "PB15_28") (pintype "bidirectional+no_connect"))
    )
    (net (code "65") (name "unconnected-(U2-PC15-Pad4)") (class "Default")
      (node (ref "U2") (pin "4") (pinfunction "PC15_4") (pintype "bidirectional+no_connect"))
    )
  )
)
